# EFR32BG24B110F1536IM48-B.net
KiCad netlist of a schematic drawn in Altium Designer
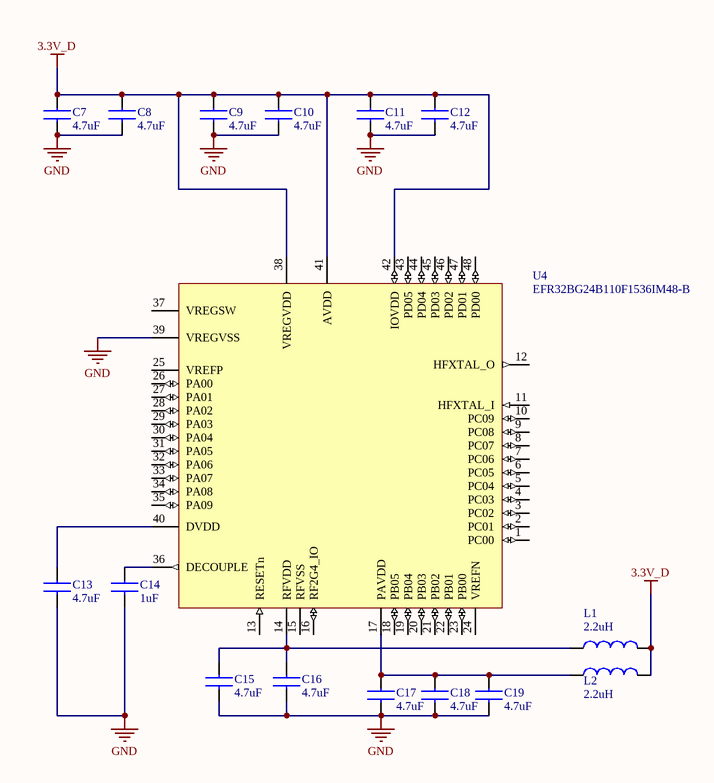
[diagram p0: EFR32BG24B110F1536IM48-B.SchDoc]

(export (version "E")
  (design (tool "Eeschema 10.0.6"))
  (components
    (comp (ref "C7")
      (value "4.7uF")
      (footprint "C_0603")
      (description "CAP CER 4.7UF 10V X5R 0603")
      (fields
        (field (name "MANUFACTURER") "Murata")
        (field (name "MANUFACTURER PART NUMBER") "GRM188R61A475KAAJD")
      )
      (libsource (lib "LPEDT_Parts") (part "C_4.7U_0603"))
    )
    (comp (ref "C8")
      (value "4.7uF")
      (footprint "C_0603")
      (description "CAP CER 4.7UF 10V X5R 0603")
      (fields
        (field (name "MANUFACTURER") "Murata")
        (field (name "MANUFACTURER PART NUMBER") "GRM188R61A475KAAJD")
      )
      (libsource (lib "LPEDT_Parts") (part "C_4.7U_0603"))
    )
    (comp (ref "C9")
      (value "4.7uF")
      (footprint "C_0603")
      (description "CAP CER 4.7UF 10V X5R 0603")
      (fields
        (field (name "MANUFACTURER") "Murata")
        (field (name "MANUFACTURER PART NUMBER") "GRM188R61A475KAAJD")
      )
      (libsource (lib "LPEDT_Parts") (part "C_4.7U_0603"))
    )
    (comp (ref "C10")
      (value "4.7uF")
      (footprint "C_0603")
      (description "CAP CER 4.7UF 10V X5R 0603")
      (fields
        (field (name "MANUFACTURER") "Murata")
        (field (name "MANUFACTURER PART NUMBER") "GRM188R61A475KAAJD")
      )
      (libsource (lib "LPEDT_Parts") (part "C_4.7U_0603"))
    )
    (comp (ref "C11")
      (value "4.7uF")
      (footprint "C_0603")
      (description "CAP CER 4.7UF 10V X5R 0603")
      (fields
        (field (name "MANUFACTURER") "Murata")
        (field (name "MANUFACTURER PART NUMBER") "GRM188R61A475KAAJD")
      )
      (libsource (lib "LPEDT_Parts") (part "C_4.7U_0603"))
    )
    (comp (ref "C12")
      (value "4.7uF")
      (footprint "C_0603")
      (description "CAP CER 4.7UF 10V X5R 0603")
      (fields
        (field (name "MANUFACTURER") "Murata")
        (field (name "MANUFACTURER PART NUMBER") "GRM188R61A475KAAJD")
      )
      (libsource (lib "LPEDT_Parts") (part "C_4.7U_0603"))
    )
    (comp (ref "C13")
      (value "4.7uF")
      (footprint "C_0603")
      (description "CAP CER 4.7UF 10V X5R 0603")
      (fields
        (field (name "MANUFACTURER") "Murata")
        (field (name "MANUFACTURER PART NUMBER") "GRM188R61A475KAAJD")
      )
      (libsource (lib "LPEDT_Parts") (part "C_4.7U_0603"))
    )
    (comp (ref "C14")
      (value "1uF")
      (footprint "C_0603")
      (description "CAP CER 1UF 10V X5R 0603")
      (fields
        (field (name "MANUFACTURER") "Murata")
        (field (name "MANUFACTURER PART NUMBER") "GRM188R61A105KA61D")
      )
      (libsource (lib "LPEDT_Parts") (part "C_1U_0603"))
    )
    (comp (ref "C15")
      (value "4.7uF")
      (footprint "C_0603")
      (description "CAP CER 4.7UF 10V X5R 0603")
      (fields
        (field (name "MANUFACTURER") "Murata")
        (field (name "MANUFACTURER PART NUMBER") "GRM188R61A475KAAJD")
      )
      (libsource (lib "LPEDT_Parts") (part "C_4.7U_0603"))
    )
    (comp (ref "C16")
      (value "4.7uF")
      (footprint "C_0603")
      (description "CAP CER 4.7UF 10V X5R 0603")
      (fields
        (field (name "MANUFACTURER") "Murata")
        (field (name "MANUFACTURER PART NUMBER") "GRM188R61A475KAAJD")
      )
      (libsource (lib "LPEDT_Parts") (part "C_4.7U_0603"))
    )
    (comp (ref "C17")
      (value "4.7uF")
      (footprint "C_0603")
      (description "CAP CER 4.7UF 10V X5R 0603")
      (fields
        (field (name "MANUFACTURER") "Murata")
        (field (name "MANUFACTURER PART NUMBER") "GRM188R61A475KAAJD")
      )
      (libsource (lib "LPEDT_Parts") (part "C_4.7U_0603"))
    )
    (comp (ref "C18")
      (value "4.7uF")
      (footprint "C_0603")
      (description "CAP CER 4.7UF 10V X5R 0603")
      (fields
        (field (name "MANUFACTURER") "Murata")
        (field (name "MANUFACTURER PART NUMBER") "GRM188R61A475KAAJD")
      )
      (libsource (lib "LPEDT_Parts") (part "C_4.7U_0603"))
    )
    (comp (ref "C19")
      (value "4.7uF")
      (footprint "C_0603")
      (description "CAP CER 4.7UF 10V X5R 0603")
      (fields
        (field (name "MANUFACTURER") "Murata")
        (field (name "MANUFACTURER PART NUMBER") "GRM188R61A475KAAJD")
      )
      (libsource (lib "LPEDT_Parts") (part "C_4.7U_0603"))
    )
    (comp (ref "L1")
      (value "2.2uH")
      (footprint "L_0603")
      (description "General Purpose Inductor, 2.2uH, 20%, 1 Element, Ferrite-Core, SMD, 0603")
      (fields
        (field (name "MANUFACTURER") "Murata")
        (field (name "MANUFACTURER PART NUMBER") "LQM18PN2R2MGHD")
      )
      (libsource (lib "LPEDT_Parts") (part "L_2.2U"))
    )
    (comp (ref "L2")
      (value "2.2uH")
      (footprint "L_0603")
      (description "General Purpose Inductor, 2.2uH, 20%, 1 Element, Ferrite-Core, SMD, 0603")
      (fields
        (field (name "MANUFACTURER") "Murata")
        (field (name "MANUFACTURER PART NUMBER") "LQM18PN2R2MGHD")
      )
      (libsource (lib "LPEDT_Parts") (part "L_2.2U"))
    )
    (comp (ref "U4")
      (value "EFR32BG24B110F1536IM48-B")
      (footprint "48-QFN_6x6_2")
      (description "BG24, 2.4 GHz, 1536kB Flash, 256kB RAM, +10 dBm, Secure Vault High, 20-bit ADC +125C, QFN48")
      (fields (field (name "MANUFACTURER") "Silicon Labs"))
      (libsource (lib "LPEDT_Parts") (part "U_EFR32BG24B110F1536IM48-B"))
    )
  )
  (nets
    (net (code "1") (name "3.3V_D") (class "Default")
      (node (ref "C10") (pin "1") (pinfunction "1_1") (pintype "passive"))
      (node (ref "C11") (pin "1") (pinfunction "1_1") (pintype "passive"))
      (node (ref "C12") (pin "1") (pinfunction "1_1") (pintype "passive"))
      (node (ref "C7") (pin "1") (pinfunction "1_1") (pintype "passive"))
      (node (ref "C8") (pin "1") (pinfunction "1_1") (pintype "passive"))
      (node (ref "C9") (pin "1") (pinfunction "1_1") (pintype "passive"))
      (node (ref "L1") (pin "2") (pinfunction "2_2") (pintype "passive"))
      (node (ref "L2") (pin "2") (pinfunction "2_2") (pintype "passive"))
      (node (ref "U4") (pin "38") (pinfunction "VREGVDD_38") (pintype "power_in"))
      (node (ref "U4") (pin "41") (pinfunction "AVDD_41") (pintype "power_in"))
      (node (ref "U4") (pin "42") (pinfunction "IOVDD_42") (pintype "bidirectional"))
    )
    (net (code "2") (name "GND") (class "Default")
      (node (ref "C10") (pin "2") (pinfunction "2_2") (pintype "passive"))
      (node (ref "C11") (pin "2") (pinfunction "2_2") (pintype "passive"))
      (node (ref "C12") (pin "2") (pinfunction "2_2") (pintype "passive"))
      (node (ref "C13") (pin "1") (pinfunction "1_1") (pintype "passive"))
      (node (ref "C14") (pin "1") (pinfunction "1_1") (pintype "passive"))
      (node (ref "C15") (pin "2") (pinfunction "2_2") (pintype "passive"))
      (node (ref "C16") (pin "2") (pinfunction "2_2") (pintype "passive"))
      (node (ref "C17") (pin "2") (pinfunction "2_2") (pintype "passive"))
      (node (ref "C18") (pin "2") (pinfunction "2_2") (pintype "passive"))
      (node (ref "C19") (pin "2") (pinfunction "2_2") (pintype "passive"))
      (node (ref "C7") (pin "2") (pinfunction "2_2") (pintype "passive"))
      (node (ref "C8") (pin "2") (pinfunction "2_2") (pintype "passive"))
      (node (ref "C9") (pin "2") (pinfunction "2_2") (pintype "passive"))
      (node (ref "U4") (pin "39") (pinfunction "VREGVSS_39") (pintype "power_in"))
    )
    (net (code "3") (name "Net-(U4-DECOUPLE)") (class "Default")
      (node (ref "C14") (pin "2") (pinfunction "2_2") (pintype "passive"))
      (node (ref "U4") (pin "36") (pinfunction "DECOUPLE_36") (pintype "output"))
    )
    (net (code "4") (name "Net-(U4-DVDD)") (class "Default")
      (node (ref "C13") (pin "2") (pinfunction "2_2") (pintype "passive"))
      (node (ref "U4") (pin "40") (pinfunction "DVDD_40") (pintype "power_in"))
    )
    (net (code "5") (name "Net-(U4-PAVDD)") (class "Default")
      (node (ref "C17") (pin "1") (pinfunction "1_1") (pintype "passive"))
      (node (ref "C18") (pin "1") (pinfunction "1_1") (pintype "passive"))
      (node (ref "C19") (pin "1") (pinfunction "1_1") (pintype "passive"))
      (node (ref "L2") (pin "1") (pinfunction "1_1") (pintype "passive"))
      (node (ref "U4") (pin "17") (pinfunction "PAVDD_17") (pintype "power_in"))
    )
    (net (code "6") (name "Net-(U4-RFVDD)") (class "Default")
      (node (ref "C15") (pin "1") (pinfunction "1_1") (pintype "passive"))
      (node (ref "C16") (pin "1") (pinfunction "1_1") (pintype "passive"))
      (node (ref "L1") (pin "1") (pinfunction "1_1") (pintype "passive"))
      (node (ref "U4") (pin "14") (pinfunction "RFVDD_14") (pintype "power_in"))
    )
    (net (code "7") (name "unconnected-(U4-HFXTAL_I-Pad11)") (class "Default")
      (node (ref "U4") (pin "11") (pinfunction "HFXTAL_I_11") (pintype "input"))
    )
    (net (code "8") (name "unconnected-(U4-HFXTAL_O-Pad12)") (class "Default")
      (node (ref "U4") (pin "12") (pinfunction "HFXTAL_O_12") (pintype "output"))
    )
    (net (code "9") (name "unconnected-(U4-PA00-Pad26)") (class "Default")
      (node (ref "U4") (pin "26") (pinfunction "PA00_26") (pintype "bidirectional"))
    )
    (net (code "10") (name "unconnected-(U4-PA01-Pad27)") (class "Default")
      (node (ref "U4") (pin "27") (pinfunction "PA01_27") (pintype "bidirectional"))
    )
    (net (code "11") (name "unconnected-(U4-PA02-Pad28)") (class "Default")
      (node (ref "U4") (pin "28") (pinfunction "PA02_28") (pintype "bidirectional"))
    )
    (net (code "12") (name "unconnected-(U4-PA03-Pad29)") (class "Default")
      (node (ref "U4") (pin "29") (pinfunction "PA03_29") (pintype "bidirectional"))
    )
    (net (code "13") (name "unconnected-(U4-PA04-Pad30)") (class "Default")
      (node (ref "U4") (pin "30") (pinfunction "PA04_30") (pintype "bidirectional"))
    )
    (net (code "14") (name "unconnected-(U4-PA05-Pad31)") (class "Default")
      (node (ref "U4") (pin "31") (pinfunction "PA05_31") (pintype "bidirectional"))
    )
    (net (code "15") (name "unconnected-(U4-PA06-Pad32)") (class "Default")
      (node (ref "U4") (pin "32") (pinfunction "PA06_32") (pintype "bidirectional"))
    )
    (net (code "16") (name "unconnected-(U4-PA07-Pad33)") (class "Default")
      (node (ref "U4") (pin "33") (pinfunction "PA07_33") (pintype "bidirectional"))
    )
    (net (code "17") (name "unconnected-(U4-PA08-Pad34)") (class "Default")
      (node (ref "U4") (pin "34") (pinfunction "PA08_34") (pintype "bidirectional"))
    )
    (net (code "18") (name "unconnected-(U4-PA09-Pad35)") (class "Default")
      (node (ref "U4") (pin "35") (pinfunction "PA09_35") (pintype "bidirectional"))
    )
    (net (code "19") (name "unconnected-(U4-PB00-Pad23)") (class "Default")
      (node (ref "U4") (pin "23") (pinfunction "PB00_23") (pintype "bidirectional"))
    )
    (net (code "20") (name "unconnected-(U4-PB01-Pad22)") (class "Default")
      (node (ref "U4") (pin "22") (pinfunction "PB01_22") (pintype "bidirectional"))
    )
    (net (code "21") (name "unconnected-(U4-PB02-Pad21)") (class "Default")
      (node (ref "U4") (pin "21") (pinfunction "PB02_21") (pintype "bidirectional"))
    )
    (net (code "22") (name "unconnected-(U4-PB03-Pad20)") (class "Default")
      (node (ref "U4") (pin "20") (pinfunction "PB03_20") (pintype "bidirectional"))
    )
    (net (code "23") (name "unconnected-(U4-PB04-Pad19)") (class "Default")
      (node (ref "U4") (pin "19") (pinfunction "PB04_19") (pintype "bidirectional"))
    )
    (net (code "24") (name "unconnected-(U4-PB05-Pad18)") (class "Default")
      (node (ref "U4") (pin "18") (pinfunction "PB05_18") (pintype "bidirectional"))
    )
    (net (code "25") (name "unconnected-(U4-PC00-Pad1)") (class "Default")
      (node (ref "U4") (pin "1") (pinfunction "PC00_1") (pintype "bidirectional"))
    )
    (net (code "26") (name "unconnected-(U4-PC01-Pad2)") (class "Default")
      (node (ref "U4") (pin "2") (pinfunction "PC01_2") (pintype "bidirectional"))
    )
    (net (code "27") (name "unconnected-(U4-PC02-Pad3)") (class "Default")
      (node (ref "U4") (pin "3") (pinfunction "PC02_3") (pintype "bidirectional"))
    )
    (net (code "28") (name "unconnected-(U4-PC03-Pad4)") (class "Default")
      (node (ref "U4") (pin "4") (pinfunction "PC03_4") (pintype "bidirectional"))
    )
    (net (code "29") (name "unconnected-(U4-PC04-Pad5)") (class "Default")
      (node (ref "U4") (pin "5") (pinfunction "PC04_5") (pintype "bidirectional"))
    )
    (net (code "30") (name "unconnected-(U4-PC05-Pad6)") (class "Default")
      (node (ref "U4") (pin "6") (pinfunction "PC05_6") (pintype "bidirectional"))
    )
    (net (code "31") (name "unconnected-(U4-PC06-Pad7)") (class "Default")
      (node (ref "U4") (pin "7") (pinfunction "PC06_7") (pintype "bidirectional"))
    )
    (net (code "32") (name "unconnected-(U4-PC07-Pad8)") (class "Default")
      (node (ref "U4") (pin "8") (pinfunction "PC07_8") (pintype "bidirectional"))
    )
    (net (code "33") (name "unconnected-(U4-PC08-Pad9)") (class "Default")
      (node (ref "U4") (pin "9") (pinfunction "PC08_9") (pintype "bidirectional"))
    )
    (net (code "34") (name "unconnected-(U4-PC09-Pad10)") (class "Default")
      (node (ref "U4") (pin "10") (pinfunction "PC09_10") (pintype "bidirectional"))
    )
    (net (code "35") (name "unconnected-(U4-PD00-Pad48)") (class "Default")
      (node (ref "U4") (pin "48") (pinfunction "PD00_48") (pintype "bidirectional"))
    )
    (net (code "36") (name "unconnected-(U4-PD01-Pad47)") (class "Default")
      (node (ref "U4") (pin "47") (pinfunction "PD01_47") (pintype "bidirectional"))
    )
    (net (code "37") (name "unconnected-(U4-PD02-Pad46)") (class "Default")
      (node (ref "U4") (pin "46") (pinfunction "PD02_46") (pintype "bidirectional"))
    )
    (net (code "38") (name "unconnected-(U4-PD03-Pad45)") (class "Default")
      (node (ref "U4") (pin "45") (pinfunction "PD03_45") (pintype "bidirectional"))
    )
    (net (code "39") (name "unconnected-(U4-PD04-Pad44)") (class "Default")
      (node (ref "U4") (pin "44") (pinfunction "PD04_44") (pintype "bidirectional"))
    )
    (net (code "40") (name "unconnected-(U4-PD05-Pad43)") (class "Default")
      (node (ref "U4") (pin "43") (pinfunction "PD05_43") (pintype "bidirectional"))
    )
    (net (code "41") (name "unconnected-(U4-RESETn-Pad13)") (class "Default")
      (node (ref "U4") (pin "13") (pinfunction "RESETn_13") (pintype "input"))
    )
    (net (code "42") (name "unconnected-(U4-RF2G4_IO-Pad16)") (class "Default")
      (node (ref "U4") (pin "16") (pinfunction "RF2G4_IO_16") (pintype "bidirectional"))
    )
    (net (code "43") (name "unconnected-(U4-RFVSS-Pad15)") (class "Default")
      (node (ref "U4") (pin "15") (pinfunction "RFVSS_15") (pintype "power_in"))
    )
    (net (code "44") (name "unconnected-(U4-VREFN-Pad24)") (class "Default")
      (node (ref "U4") (pin "24") (pinfunction "VREFN_24") (pintype "power_in"))
    )
    (net (code "45") (name "unconnected-(U4-VREFP-Pad25)") (class "Default")
      (node (ref "U4") (pin "25") (pinfunction "VREFP_25") (pintype "power_in"))
    )
    (net (code "46") (name "unconnected-(U4-VREGSW-Pad37)") (class "Default")
      (node (ref "U4") (pin "37") (pinfunction "VREGSW_37") (pintype "power_in"))
    )
  )
)
